# Circuit_Etudiant_2023.net
KiCad netlist of a schematic drawn in Altium Designer
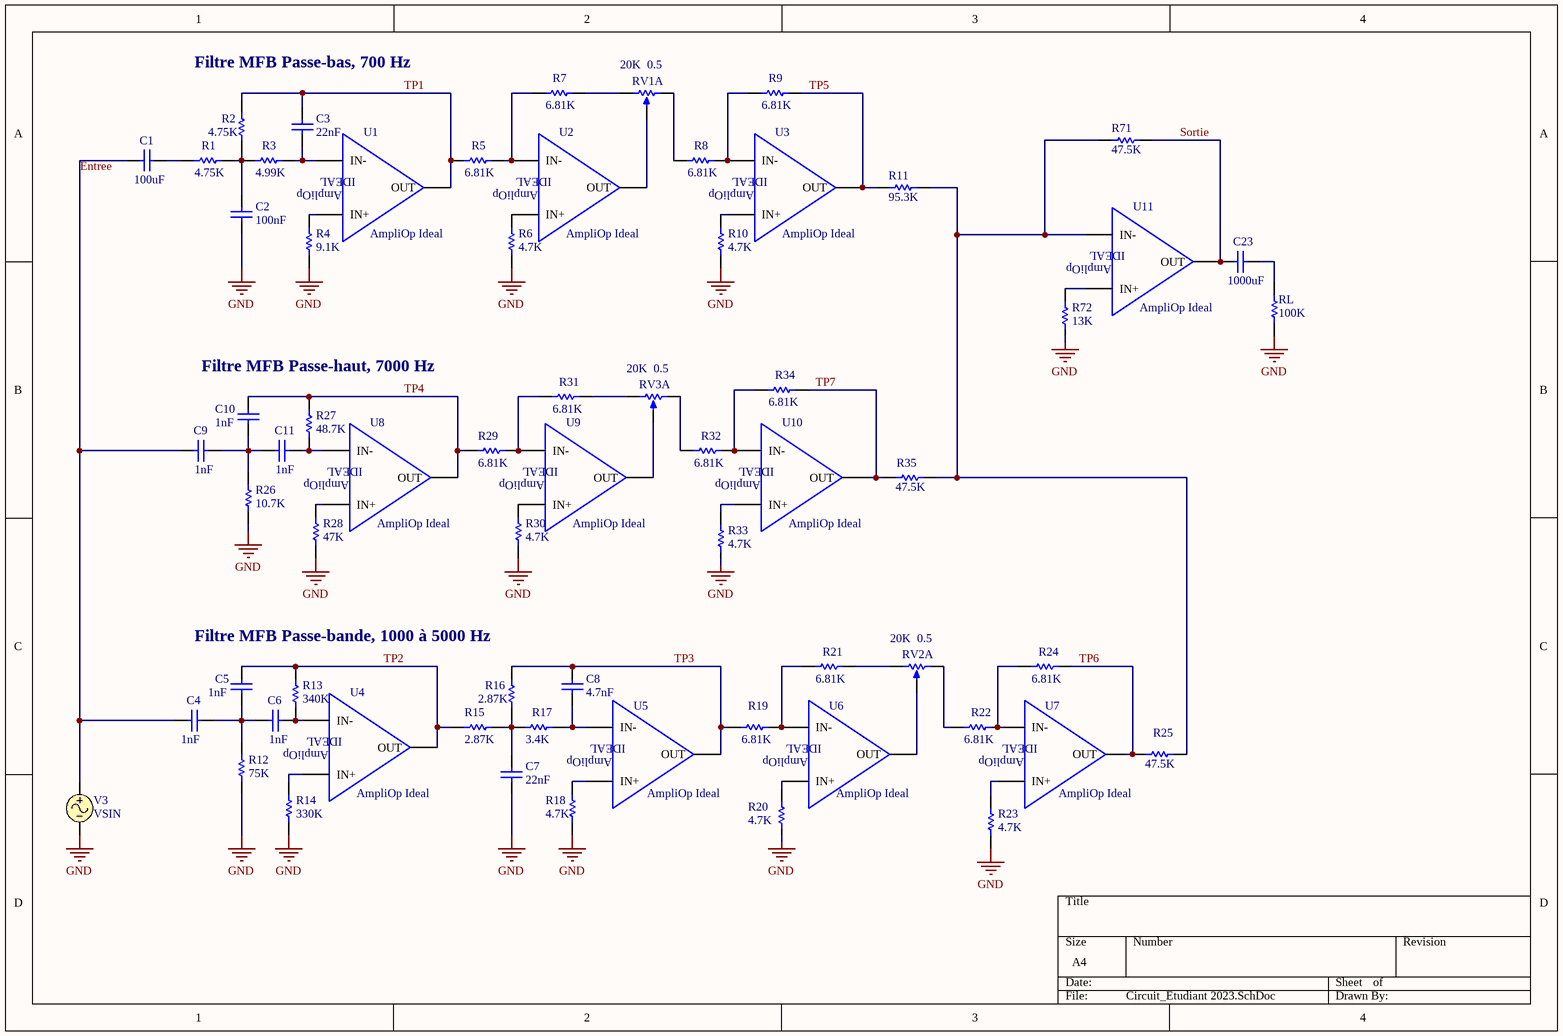
[diagram p0: Circuit_Etudiant 2023.SchDoc]

(export (version "E")
  (design (tool "Eeschema 10.0.6"))
  (components
    (comp (ref "C1")
      (value "100uF")
      (footprint "RAD-0.3")
      (description "Capacitor")
      (fields (field (name "Comment") "Cap") (field (name "PUBLISHER") "Altium Limited"))
      (libsource (lib "Miscellaneous Devices") (part "Cap"))
    )
    (comp (ref "C2")
      (value "100nF")
      (footprint "RAD-0.3")
      (description "Capacitor")
      (fields (field (name "Comment") "Cap") (field (name "PUBLISHER") "Altium Limited"))
      (libsource (lib "Miscellaneous Devices") (part "Cap"))
    )
    (comp (ref "C3")
      (value "22nF")
      (footprint "RAD-0.3")
      (description "Capacitor")
      (fields (field (name "Comment") "Cap") (field (name "PUBLISHER") "Altium Limited"))
      (libsource (lib "Miscellaneous Devices") (part "Cap"))
    )
    (comp (ref "C4")
      (value "1nF")
      (footprint "RAD-0.3")
      (description "Capacitor")
      (fields (field (name "Comment") "Cap") (field (name "PUBLISHER") "Altium Limited"))
      (libsource (lib "Miscellaneous Devices") (part "Cap"))
    )
    (comp (ref "C5")
      (value "1nF")
      (footprint "RAD-0.3")
      (description "Capacitor")
      (fields (field (name "Comment") "Cap") (field (name "PUBLISHER") "Altium Limited"))
      (libsource (lib "Miscellaneous Devices") (part "Cap"))
    )
    (comp (ref "C6")
      (value "1nF")
      (footprint "RAD-0.3")
      (description "Capacitor")
      (fields (field (name "Comment") "Cap") (field (name "PUBLISHER") "Altium Limited"))
      (libsource (lib "Miscellaneous Devices") (part "Cap"))
    )
    (comp (ref "C7")
      (value "22nF")
      (footprint "RAD-0.3")
      (description "Capacitor")
      (fields (field (name "Comment") "Cap") (field (name "PUBLISHER") "Altium Limited"))
      (libsource (lib "Miscellaneous Devices") (part "Cap"))
    )
    (comp (ref "C8")
      (value "4.7nF")
      (footprint "RAD-0.3")
      (description "Capacitor")
      (fields (field (name "Comment") "Cap") (field (name "PUBLISHER") "Altium Limited"))
      (libsource (lib "Miscellaneous Devices") (part "Cap"))
    )
    (comp (ref "C9")
      (value "1nF")
      (footprint "RAD-0.3")
      (description "Capacitor")
      (fields (field (name "Comment") "Cap") (field (name "PUBLISHER") "Altium Limited"))
      (libsource (lib "Miscellaneous Devices") (part "Cap"))
    )
    (comp (ref "C10")
      (value "1nF")
      (footprint "RAD-0.3")
      (description "Capacitor")
      (fields (field (name "Comment") "Cap") (field (name "PUBLISHER") "Altium Limited"))
      (libsource (lib "Miscellaneous Devices") (part "Cap"))
    )
    (comp (ref "C11")
      (value "1nF")
      (footprint "RAD-0.3")
      (description "Capacitor")
      (fields (field (name "Comment") "Cap") (field (name "PUBLISHER") "Altium Limited"))
      (libsource (lib "Miscellaneous Devices") (part "Cap"))
    )
    (comp (ref "C23")
      (value "1000uF")
      (footprint "RAD-0.3")
      (description "Capacitor")
      (fields (field (name "Comment") "Cap") (field (name "PUBLISHER") "Altium Limited"))
      (libsource (lib "Miscellaneous Devices") (part "Cap"))
    )
    (comp (ref "R1")
      (value "4.75K")
      (footprint "AXIAL-0.3")
      (description "Resistor")
      (fields (field (name "Comment") "Res1") (field (name "PUBLISHER") "Altium Limited"))
      (libsource (lib "Miscellaneous Devices") (part "Res1"))
    )
    (comp (ref "R2")
      (value "4.75K")
      (footprint "AXIAL-0.3")
      (description "Resistor")
      (fields (field (name "Comment") "Res1") (field (name "PUBLISHER") "Altium Limited"))
      (libsource (lib "Miscellaneous Devices") (part "Res1"))
    )
    (comp (ref "R3")
      (value "4.99K")
      (footprint "AXIAL-0.3")
      (description "Resistor")
      (fields (field (name "Comment") "Res1") (field (name "PUBLISHER") "Altium Limited"))
      (libsource (lib "Miscellaneous Devices") (part "Res1"))
    )
    (comp (ref "R4")
      (value "9.1K")
      (footprint "AXIAL-0.3")
      (description "Resistor")
      (fields (field (name "Comment") "Res1") (field (name "PUBLISHER") "Altium Limited"))
      (libsource (lib "Miscellaneous Devices") (part "Res1"))
    )
    (comp (ref "R5")
      (value "6.81K")
      (footprint "AXIAL-0.3")
      (description "Resistor")
      (fields (field (name "Comment") "Res1") (field (name "PUBLISHER") "Altium Limited"))
      (libsource (lib "Miscellaneous Devices") (part "Res1"))
    )
    (comp (ref "R6")
      (value "4.7K")
      (footprint "AXIAL-0.3")
      (description "Resistor")
      (fields (field (name "Comment") "Res1") (field (name "PUBLISHER") "Altium Limited"))
      (libsource (lib "Miscellaneous Devices") (part "Res1"))
    )
    (comp (ref "R7")
      (value "6.81K")
      (footprint "AXIAL-0.3")
      (description "Resistor")
      (fields (field (name "Comment") "Res1") (field (name "PUBLISHER") "Altium Limited"))
      (libsource (lib "Miscellaneous Devices") (part "Res1"))
    )
    (comp (ref "R8")
      (value "6.81K")
      (footprint "AXIAL-0.3")
      (description "Resistor")
      (fields (field (name "Comment") "Res1") (field (name "PUBLISHER") "Altium Limited"))
      (libsource (lib "Miscellaneous Devices") (part "Res1"))
    )
    (comp (ref "R9")
      (value "6.81K")
      (footprint "AXIAL-0.3")
      (description "Resistor")
      (fields (field (name "Comment") "Res1") (field (name "PUBLISHER") "Altium Limited"))
      (libsource (lib "Miscellaneous Devices") (part "Res1"))
    )
    (comp (ref "R10")
      (value "4.7K")
      (footprint "AXIAL-0.3")
      (description "Resistor")
      (fields (field (name "Comment") "Res1") (field (name "PUBLISHER") "Altium Limited"))
      (libsource (lib "Miscellaneous Devices") (part "Res1"))
    )
    (comp (ref "R11")
      (value "95.3K")
      (footprint "AXIAL-0.3")
      (description "Resistor")
      (fields (field (name "Comment") "Res1") (field (name "PUBLISHER") "Altium Limited"))
      (libsource (lib "Miscellaneous Devices") (part "Res1"))
    )
    (comp (ref "R12")
      (value "75K")
      (footprint "AXIAL-0.3")
      (description "Resistor")
      (fields (field (name "Comment") "Res1") (field (name "PUBLISHER") "Altium Limited"))
      (libsource (lib "Miscellaneous Devices") (part "Res1"))
    )
    (comp (ref "R13")
      (value "340K")
      (footprint "AXIAL-0.3")
      (description "Resistor")
      (fields (field (name "Comment") "Res1") (field (name "PUBLISHER") "Altium Limited"))
      (libsource (lib "Miscellaneous Devices") (part "Res1"))
    )
    (comp (ref "R14")
      (value "330K")
      (footprint "AXIAL-0.3")
      (description "Resistor")
      (fields (field (name "Comment") "Res1") (field (name "PUBLISHER") "Altium Limited"))
      (libsource (lib "Miscellaneous Devices") (part "Res1"))
    )
    (comp (ref "R15")
      (value "2.87K")
      (footprint "AXIAL-0.3")
      (description "Resistor")
      (fields (field (name "Comment") "Res1") (field (name "PUBLISHER") "Altium Limited"))
      (libsource (lib "Miscellaneous Devices") (part "Res1"))
    )
    (comp (ref "R16")
      (value "2.87K")
      (footprint "AXIAL-0.3")
      (description "Resistor")
      (fields (field (name "Comment") "Res1") (field (name "PUBLISHER") "Altium Limited"))
      (libsource (lib "Miscellaneous Devices") (part "Res1"))
    )
    (comp (ref "R17")
      (value "3.4K")
      (footprint "AXIAL-0.3")
      (description "Resistor")
      (fields (field (name "Comment") "Res1") (field (name "PUBLISHER") "Altium Limited"))
      (libsource (lib "Miscellaneous Devices") (part "Res1"))
    )
    (comp (ref "R18")
      (value "4.7K")
      (footprint "AXIAL-0.3")
      (description "Resistor")
      (fields (field (name "Comment") "Res1") (field (name "PUBLISHER") "Altium Limited"))
      (libsource (lib "Miscellaneous Devices") (part "Res1"))
    )
    (comp (ref "R19")
      (value "6.81K")
      (footprint "AXIAL-0.3")
      (description "Resistor")
      (fields (field (name "Comment") "Res1") (field (name "PUBLISHER") "Altium Limited"))
      (libsource (lib "Miscellaneous Devices") (part "Res1"))
    )
    (comp (ref "R20")
      (value "4.7K")
      (footprint "AXIAL-0.3")
      (description "Resistor")
      (fields (field (name "Comment") "Res1") (field (name "PUBLISHER") "Altium Limited"))
      (libsource (lib "Miscellaneous Devices") (part "Res1"))
    )
    (comp (ref "R21")
      (value "6.81K")
      (footprint "AXIAL-0.3")
      (description "Resistor")
      (fields (field (name "Comment") "Res1") (field (name "PUBLISHER") "Altium Limited"))
      (libsource (lib "Miscellaneous Devices") (part "Res1"))
    )
    (comp (ref "R22")
      (value "6.81K")
      (footprint "AXIAL-0.3")
      (description "Resistor")
      (fields (field (name "Comment") "Res1") (field (name "PUBLISHER") "Altium Limited"))
      (libsource (lib "Miscellaneous Devices") (part "Res1"))
    )
    (comp (ref "R23")
      (value "4.7K")
      (footprint "AXIAL-0.3")
      (description "Resistor")
      (fields (field (name "Comment") "Res1") (field (name "PUBLISHER") "Altium Limited"))
      (libsource (lib "Miscellaneous Devices") (part "Res1"))
    )
    (comp (ref "R24")
      (value "6.81K")
      (footprint "AXIAL-0.3")
      (description "Resistor")
      (fields (field (name "Comment") "Res1") (field (name "PUBLISHER") "Altium Limited"))
      (libsource (lib "Miscellaneous Devices") (part "Res1"))
    )
    (comp (ref "R25")
      (value "47.5K")
      (footprint "AXIAL-0.3")
      (description "Resistor")
      (fields (field (name "Comment") "Res1") (field (name "PUBLISHER") "Altium Limited"))
      (libsource (lib "Miscellaneous Devices") (part "Res1"))
    )
    (comp (ref "R26")
      (value "10.7K")
      (footprint "AXIAL-0.3")
      (description "Resistor")
      (fields (field (name "Comment") "Res1") (field (name "PUBLISHER") "Altium Limited"))
      (libsource (lib "Miscellaneous Devices") (part "Res1"))
    )
    (comp (ref "R27")
      (value "48.7K")
      (footprint "AXIAL-0.3")
      (description "Resistor")
      (fields (field (name "Comment") "Res1") (field (name "PUBLISHER") "Altium Limited"))
      (libsource (lib "Miscellaneous Devices") (part "Res1"))
    )
    (comp (ref "R28")
      (value "47K")
      (footprint "AXIAL-0.3")
      (description "Resistor")
      (fields (field (name "Comment") "Res1") (field (name "PUBLISHER") "Altium Limited"))
      (libsource (lib "Miscellaneous Devices") (part "Res1"))
    )
    (comp (ref "R29")
      (value "6.81K")
      (footprint "AXIAL-0.3")
      (description "Resistor")
      (fields (field (name "Comment") "Res1") (field (name "PUBLISHER") "Altium Limited"))
      (libsource (lib "Miscellaneous Devices") (part "Res1"))
    )
    (comp (ref "R30")
      (value "4.7K")
      (footprint "AXIAL-0.3")
      (description "Resistor")
      (fields (field (name "Comment") "Res1") (field (name "PUBLISHER") "Altium Limited"))
      (libsource (lib "Miscellaneous Devices") (part "Res1"))
    )
    (comp (ref "R31")
      (value "6.81K")
      (footprint "AXIAL-0.3")
      (description "Resistor")
      (fields (field (name "Comment") "Res1") (field (name "PUBLISHER") "Altium Limited"))
      (libsource (lib "Miscellaneous Devices") (part "Res1"))
    )
    (comp (ref "R32")
      (value "6.81K")
      (footprint "AXIAL-0.3")
      (description "Resistor")
      (fields (field (name "Comment") "Res1") (field (name "PUBLISHER") "Altium Limited"))
      (libsource (lib "Miscellaneous Devices") (part "Res1"))
    )
    (comp (ref "R33")
      (value "4.7K")
      (footprint "AXIAL-0.3")
      (description "Resistor")
      (fields (field (name "Comment") "Res1") (field (name "PUBLISHER") "Altium Limited"))
      (libsource (lib "Miscellaneous Devices") (part "Res1"))
    )
    (comp (ref "R34")
      (value "6.81K")
      (footprint "AXIAL-0.3")
      (description "Resistor")
      (fields (field (name "Comment") "Res1") (field (name "PUBLISHER") "Altium Limited"))
      (libsource (lib "Miscellaneous Devices") (part "Res1"))
    )
    (comp (ref "R35")
      (value "47.5K")
      (footprint "AXIAL-0.3")
      (description "Resistor")
      (fields (field (name "Comment") "Res1") (field (name "PUBLISHER") "Altium Limited"))
      (libsource (lib "Miscellaneous Devices") (part "Res1"))
    )
    (comp (ref "R71")
      (value "47.5K")
      (footprint "AXIAL-0.3")
      (description "Resistor")
      (fields (field (name "Comment") "Res1") (field (name "PUBLISHER") "Altium Limited"))
      (libsource (lib "Miscellaneous Devices") (part "Res1"))
    )
    (comp (ref "R72")
      (value "13K")
      (footprint "AXIAL-0.3")
      (description "Resistor")
      (fields (field (name "Comment") "Res1") (field (name "PUBLISHER") "Altium Limited"))
      (libsource (lib "Miscellaneous Devices") (part "Res1"))
    )
    (comp (ref "RL")
      (value "100K")
      (footprint "AXIAL-0.3")
      (description "Resistor")
      (fields (field (name "Comment") "Res1") (field (name "PUBLISHER") "Altium Limited"))
      (libsource (lib "Miscellaneous Devices") (part "Res1"))
    )
    (comp (ref "RV1A")
      (value "20K")
      (footprint "VR5")
      (description "Potentiometer")
      (fields
        (field (name "SET POSITION") "0.5")
        (field (name "Comment") "RPot")
        (field (name "PUBLISHER") "Altium Limited")
      )
      (libsource (lib "Miscellaneous Devices") (part "RPot"))
    )
    (comp (ref "RV2A")
      (value "20K")
      (footprint "VR5")
      (description "Potentiometer")
      (fields
        (field (name "SET POSITION") "0.5")
        (field (name "Comment") "RPot")
        (field (name "PUBLISHER") "Altium Limited")
      )
      (libsource (lib "Miscellaneous Devices") (part "RPot"))
    )
    (comp (ref "RV3A")
      (value "20K")
      (footprint "VR5")
      (description "Potentiometer")
      (fields
        (field (name "SET POSITION") "0.5")
        (field (name "Comment") "RPot")
        (field (name "PUBLISHER") "Altium Limited")
      )
      (libsource (lib "Miscellaneous Devices") (part "RPot"))
    )
    (comp (ref "U1") (value "AmpliOp Ideal") (libsource (lib "Librarie_S2") (part "AmpliOp_ideal")))
    (comp (ref "U2") (value "AmpliOp Ideal") (libsource (lib "Librarie_S2") (part "AmpliOp_ideal")))
    (comp (ref "U3") (value "AmpliOp Ideal") (libsource (lib "Librarie_S2") (part "AmpliOp_ideal")))
    (comp (ref "U4") (value "AmpliOp Ideal") (libsource (lib "Librarie_S2") (part "AmpliOp_ideal")))
    (comp (ref "U5") (value "AmpliOp Ideal") (libsource (lib "Librarie_S2") (part "AmpliOp_ideal")))
    (comp (ref "U6") (value "AmpliOp Ideal") (libsource (lib "Librarie_S2") (part "AmpliOp_ideal")))
    (comp (ref "U7") (value "AmpliOp Ideal") (libsource (lib "Librarie_S2") (part "AmpliOp_ideal")))
    (comp (ref "U8") (value "AmpliOp Ideal") (libsource (lib "Librarie_S2") (part "AmpliOp_ideal")))
    (comp (ref "U9") (value "AmpliOp Ideal") (libsource (lib "Librarie_S2") (part "AmpliOp_ideal")))
    (comp (ref "U10") (value "AmpliOp Ideal") (libsource (lib "Librarie_S2") (part "AmpliOp_ideal")))
    (comp (ref "U11") (value "AmpliOp Ideal") (libsource (lib "Librarie_S2") (part "AmpliOp_ideal")))
    (comp (ref "V3")
      (value "VSIN")
      (description "Sinusoidal Voltage Source")
      (fields (field (name "PUBLISHER") "Altium Limited"))
      (libsource (lib "Simulation Sources") (part "VSIN"))
    )
  )
  (nets
    (net (code "1") (name "/Entree") (class "Default")
      (node (ref "C1") (pin "1") (pinfunction "1_1") (pintype "passive"))
      (node (ref "C4") (pin "1") (pinfunction "1_1") (pintype "passive"))
      (node (ref "C9") (pin "1") (pinfunction "1_1") (pintype "passive"))
      (node (ref "V3") (pin "1") (pinfunction "1_1") (pintype "passive"))
    )
    (net (code "2") (name "/Sortie") (class "Default")
      (node (ref "C23") (pin "1") (pinfunction "1_1") (pintype "passive"))
      (node (ref "R71") (pin "2") (pinfunction "2_2") (pintype "passive"))
      (node (ref "U11") (pin "3") (pinfunction "OUT_3") (pintype "passive"))
    )
    (net (code "3") (name "/TP1") (class "Default")
      (node (ref "C3") (pin "1") (pinfunction "1_1") (pintype "passive"))
      (node (ref "R2") (pin "1") (pinfunction "1_1") (pintype "passive"))
      (node (ref "R5") (pin "1") (pinfunction "1_1") (pintype "passive"))
      (node (ref "U1") (pin "3") (pinfunction "OUT_3") (pintype "passive"))
    )
    (net (code "4") (name "/TP2") (class "Default")
      (node (ref "C5") (pin "1") (pinfunction "1_1") (pintype "passive"))
      (node (ref "R13") (pin "1") (pinfunction "1_1") (pintype "passive"))
      (node (ref "R15") (pin "1") (pinfunction "1_1") (pintype "passive"))
      (node (ref "U4") (pin "3") (pinfunction "OUT_3") (pintype "passive"))
    )
    (net (code "5") (name "/TP3") (class "Default")
      (node (ref "C8") (pin "1") (pinfunction "1_1") (pintype "passive"))
      (node (ref "R16") (pin "1") (pinfunction "1_1") (pintype "passive"))
      (node (ref "R19") (pin "1") (pinfunction "1_1") (pintype "passive"))
      (node (ref "U5") (pin "3") (pinfunction "OUT_3") (pintype "passive"))
    )
    (net (code "6") (name "/TP4") (class "Default")
      (node (ref "C10") (pin "1") (pinfunction "1_1") (pintype "passive"))
      (node (ref "R27") (pin "1") (pinfunction "1_1") (pintype "passive"))
      (node (ref "R29") (pin "1") (pinfunction "1_1") (pintype "passive"))
      (node (ref "U8") (pin "3") (pinfunction "OUT_3") (pintype "passive"))
    )
    (net (code "7") (name "/TP5") (class "Default")
      (node (ref "R11") (pin "1") (pinfunction "1_1") (pintype "passive"))
      (node (ref "R9") (pin "2") (pinfunction "2_2") (pintype "passive"))
      (node (ref "U3") (pin "3") (pinfunction "OUT_3") (pintype "passive"))
    )
    (net (code "8") (name "/TP6") (class "Default")
      (node (ref "R24") (pin "2") (pinfunction "2_2") (pintype "passive"))
      (node (ref "R25") (pin "1") (pinfunction "1_1") (pintype "passive"))
      (node (ref "U7") (pin "3") (pinfunction "OUT_3") (pintype "passive"))
    )
    (net (code "9") (name "/TP7") (class "Default")
      (node (ref "R34") (pin "2") (pinfunction "2_2") (pintype "passive"))
      (node (ref "R35") (pin "1") (pinfunction "1_1") (pintype "passive"))
      (node (ref "U10") (pin "3") (pinfunction "OUT_3") (pintype "passive"))
    )
    (net (code "10") (name "GND") (class "Default")
      (node (ref "C2") (pin "2") (pinfunction "2_2") (pintype "passive"))
      (node (ref "C7") (pin "2") (pinfunction "2_2") (pintype "passive"))
      (node (ref "R10") (pin "2") (pinfunction "2_2") (pintype "passive"))
      (node (ref "R12") (pin "2") (pinfunction "2_2") (pintype "passive"))
      (node (ref "R14") (pin "2") (pinfunction "2_2") (pintype "passive"))
      (node (ref "R18") (pin "2") (pinfunction "2_2") (pintype "passive"))
      (node (ref "R20") (pin "2") (pinfunction "2_2") (pintype "passive"))
      (node (ref "R23") (pin "2") (pinfunction "2_2") (pintype "passive"))
      (node (ref "R26") (pin "2") (pinfunction "2_2") (pintype "passive"))
      (node (ref "R28") (pin "2") (pinfunction "2_2") (pintype "passive"))
      (node (ref "R30") (pin "2") (pinfunction "2_2") (pintype "passive"))
      (node (ref "R33") (pin "2") (pinfunction "2_2") (pintype "passive"))
      (node (ref "R4") (pin "2") (pinfunction "2_2") (pintype "passive"))
      (node (ref "R6") (pin "2") (pinfunction "2_2") (pintype "passive"))
      (node (ref "R72") (pin "2") (pinfunction "2_2") (pintype "passive"))
      (node (ref "RL") (pin "1") (pinfunction "1_1") (pintype "passive"))
      (node (ref "V3") (pin "2") (pinfunction "2_2") (pintype "passive"))
    )
    (net (code "11") (name "Net-(C1-Pad2)") (class "Default")
      (node (ref "C1") (pin "2") (pinfunction "2_2") (pintype "passive"))
      (node (ref "R1") (pin "1") (pinfunction "1_1") (pintype "passive"))
    )
    (net (code "12") (name "Net-(C2-Pad1)") (class "Default")
      (node (ref "C2") (pin "1") (pinfunction "1_1") (pintype "passive"))
      (node (ref "R1") (pin "2") (pinfunction "2_2") (pintype "passive"))
      (node (ref "R2") (pin "2") (pinfunction "2_2") (pintype "passive"))
      (node (ref "R3") (pin "1") (pinfunction "1_1") (pintype "passive"))
    )
    (net (code "13") (name "Net-(C4-Pad2)") (class "Default")
      (node (ref "C4") (pin "2") (pinfunction "2_2") (pintype "passive"))
      (node (ref "C5") (pin "2") (pinfunction "2_2") (pintype "passive"))
      (node (ref "C6") (pin "1") (pinfunction "1_1") (pintype "passive"))
      (node (ref "R12") (pin "1") (pinfunction "1_1") (pintype "passive"))
    )
    (net (code "14") (name "Net-(C7-Pad1)") (class "Default")
      (node (ref "C7") (pin "1") (pinfunction "1_1") (pintype "passive"))
      (node (ref "R15") (pin "2") (pinfunction "2_2") (pintype "passive"))
      (node (ref "R16") (pin "2") (pinfunction "2_2") (pintype "passive"))
      (node (ref "R17") (pin "1") (pinfunction "1_1") (pintype "passive"))
    )
    (net (code "15") (name "Net-(C10-Pad2)") (class "Default")
      (node (ref "C10") (pin "2") (pinfunction "2_2") (pintype "passive"))
      (node (ref "C11") (pin "1") (pinfunction "1_1") (pintype "passive"))
      (node (ref "C9") (pin "2") (pinfunction "2_2") (pintype "passive"))
      (node (ref "R26") (pin "1") (pinfunction "1_1") (pintype "passive"))
    )
    (net (code "16") (name "Net-(C23-Pad2)") (class "Default")
      (node (ref "C23") (pin "2") (pinfunction "2_2") (pintype "passive"))
      (node (ref "RL") (pin "2") (pinfunction "2_2") (pintype "passive"))
    )
    (net (code "17") (name "Net-(RV1A-BOT)") (class "Default")
      (node (ref "R8") (pin "1") (pinfunction "1_1") (pintype "passive"))
      (node (ref "RV1A") (pin "2") (pinfunction "BOT_2") (pintype "passive"))
    )
    (net (code "18") (name "Net-(RV1A-TAP)") (class "Default")
      (node (ref "RV1A") (pin "3") (pinfunction "TAP_3") (pintype "passive"))
      (node (ref "U2") (pin "3") (pinfunction "OUT_3") (pintype "passive"))
    )
    (net (code "19") (name "Net-(RV1A-TOP)") (class "Default")
      (node (ref "R7") (pin "2") (pinfunction "2_2") (pintype "passive"))
      (node (ref "RV1A") (pin "1") (pinfunction "TOP_1") (pintype "passive"))
    )
    (net (code "20") (name "Net-(RV2A-BOT)") (class "Default")
      (node (ref "R22") (pin "1") (pinfunction "1_1") (pintype "passive"))
      (node (ref "RV2A") (pin "2") (pinfunction "BOT_2") (pintype "passive"))
    )
    (net (code "21") (name "Net-(RV2A-TAP)") (class "Default")
      (node (ref "RV2A") (pin "3") (pinfunction "TAP_3") (pintype "passive"))
      (node (ref "U6") (pin "3") (pinfunction "OUT_3") (pintype "passive"))
    )
    (net (code "22") (name "Net-(RV2A-TOP)") (class "Default")
      (node (ref "R21") (pin "2") (pinfunction "2_2") (pintype "passive"))
      (node (ref "RV2A") (pin "1") (pinfunction "TOP_1") (pintype "passive"))
    )
    (net (code "23") (name "Net-(RV3A-BOT)") (class "Default")
      (node (ref "R32") (pin "1") (pinfunction "1_1") (pintype "passive"))
      (node (ref "RV3A") (pin "2") (pinfunction "BOT_2") (pintype "passive"))
    )
    (net (code "24") (name "Net-(RV3A-TAP)") (class "Default")
      (node (ref "RV3A") (pin "3") (pinfunction "TAP_3") (pintype "passive"))
      (node (ref "U9") (pin "3") (pinfunction "OUT_3") (pintype "passive"))
    )
    (net (code "25") (name "Net-(RV3A-TOP)") (class "Default")
      (node (ref "R31") (pin "2") (pinfunction "2_2") (pintype "passive"))
      (node (ref "RV3A") (pin "1") (pinfunction "TOP_1") (pintype "passive"))
    )
    (net (code "26") (name "Net-(U1-IN+)") (class "Default")
      (node (ref "R4") (pin "1") (pinfunction "1_1") (pintype "passive"))
      (node (ref "U1") (pin "1") (pinfunction "IN+_1") (pintype "passive"))
    )
    (net (code "27") (name "Net-(U1-IN-)") (class "Default")
      (node (ref "C3") (pin "2") (pinfunction "2_2") (pintype "passive"))
      (node (ref "R3") (pin "2") (pinfunction "2_2") (pintype "passive"))
      (node (ref "U1") (pin "2") (pinfunction "IN-_2") (pintype "passive"))
    )
    (net (code "28") (name "Net-(U2-IN+)") (class "Default")
      (node (ref "R6") (pin "1") (pinfunction "1_1") (pintype "passive"))
      (node (ref "U2") (pin "1") (pinfunction "IN+_1") (pintype "passive"))
    )
    (net (code "29") (name "Net-(U2-IN-)") (class "Default")
      (node (ref "R5") (pin "2") (pinfunction "2_2") (pintype "passive"))
      (node (ref "R7") (pin "1") (pinfunction "1_1") (pintype "passive"))
      (node (ref "U2") (pin "2") (pinfunction "IN-_2") (pintype "passive"))
    )
    (net (code "30") (name "Net-(U3-IN+)") (class "Default")
      (node (ref "R10") (pin "1") (pinfunction "1_1") (pintype "passive"))
      (node (ref "U3") (pin "1") (pinfunction "IN+_1") (pintype "passive"))
    )
    (net (code "31") (name "Net-(U3-IN-)") (class "Default")
      (node (ref "R8") (pin "2") (pinfunction "2_2") (pintype "passive"))
      (node (ref "R9") (pin "1") (pinfunction "1_1") (pintype "passive"))
      (node (ref "U3") (pin "2") (pinfunction "IN-_2") (pintype "passive"))
    )
    (net (code "32") (name "Net-(U4-IN+)") (class "Default")
      (node (ref "R14") (pin "1") (pinfunction "1_1") (pintype "passive"))
      (node (ref "U4") (pin "1") (pinfunction "IN+_1") (pintype "passive"))
    )
    (net (code "33") (name "Net-(U4-IN-)") (class "Default")
      (node (ref "C6") (pin "2") (pinfunction "2_2") (pintype "passive"))
      (node (ref "R13") (pin "2") (pinfunction "2_2") (pintype "passive"))
      (node (ref "U4") (pin "2") (pinfunction "IN-_2") (pintype "passive"))
    )
    (net (code "34") (name "Net-(U5-IN+)") (class "Default")
      (node (ref "R18") (pin "1") (pinfunction "1_1") (pintype "passive"))
      (node (ref "U5") (pin "1") (pinfunction "IN+_1") (pintype "passive"))
    )
    (net (code "35") (name "Net-(U5-IN-)") (class "Default")
      (node (ref "C8") (pin "2") (pinfunction "2_2") (pintype "passive"))
      (node (ref "R17") (pin "2") (pinfunction "2_2") (pintype "passive"))
      (node (ref "U5") (pin "2") (pinfunction "IN-_2") (pintype "passive"))
    )
    (net (code "36") (name "Net-(U6-IN+)") (class "Default")
      (node (ref "R20") (pin "1") (pinfunction "1_1") (pintype "passive"))
      (node (ref "U6") (pin "1") (pinfunction "IN+_1") (pintype "passive"))
    )
    (net (code "37") (name "Net-(U6-IN-)") (class "Default")
      (node (ref "R19") (pin "2") (pinfunction "2_2") (pintype "passive"))
      (node (ref "R21") (pin "1") (pinfunction "1_1") (pintype "passive"))
      (node (ref "U6") (pin "2") (pinfunction "IN-_2") (pintype "passive"))
    )
    (net (code "38") (name "Net-(U7-IN+)") (class "Default")
      (node (ref "R23") (pin "1") (pinfunction "1_1") (pintype "passive"))
      (node (ref "U7") (pin "1") (pinfunction "IN+_1") (pintype "passive"))
    )
    (net (code "39") (name "Net-(U7-IN-)") (class "Default")
      (node (ref "R22") (pin "2") (pinfunction "2_2") (pintype "passive"))
      (node (ref "R24") (pin "1") (pinfunction "1_1") (pintype "passive"))
      (node (ref "U7") (pin "2") (pinfunction "IN-_2") (pintype "passive"))
    )
    (net (code "40") (name "Net-(U8-IN+)") (class "Default")
      (node (ref "R28") (pin "1") (pinfunction "1_1") (pintype "passive"))
      (node (ref "U8") (pin "1") (pinfunction "IN+_1") (pintype "passive"))
    )
    (net (code "41") (name "Net-(U8-IN-)") (class "Default")
      (node (ref "C11") (pin "2") (pinfunction "2_2") (pintype "passive"))
      (node (ref "R27") (pin "2") (pinfunction "2_2") (pintype "passive"))
      (node (ref "U8") (pin "2") (pinfunction "IN-_2") (pintype "passive"))
    )
    (net (code "42") (name "Net-(U9-IN+)") (class "Default")
      (node (ref "R30") (pin "1") (pinfunction "1_1") (pintype "passive"))
      (node (ref "U9") (pin "1") (pinfunction "IN+_1") (pintype "passive"))
    )
    (net (code "43") (name "Net-(U9-IN-)") (class "Default")
      (node (ref "R29") (pin "2") (pinfunction "2_2") (pintype "passive"))
      (node (ref "R31") (pin "1") (pinfunction "1_1") (pintype "passive"))
      (node (ref "U9") (pin "2") (pinfunction "IN-_2") (pintype "passive"))
    )
    (net (code "44") (name "Net-(U10-IN+)") (class "Default")
      (node (ref "R33") (pin "1") (pinfunction "1_1") (pintype "passive"))
      (node (ref "U10") (pin "1") (pinfunction "IN+_1") (pintype "passive"))
    )
    (net (code "45") (name "Net-(U10-IN-)") (class "Default")
      (node (ref "R32") (pin "2") (pinfunction "2_2") (pintype "passive"))
      (node (ref "R34") (pin "1") (pinfunction "1_1") (pintype "passive"))
      (node (ref "U10") (pin "2") (pinfunction "IN-_2") (pintype "passive"))
    )
    (net (code "46") (name "Net-(U11-IN+)") (class "Default")
      (node (ref "R72") (pin "1") (pinfunction "1_1") (pintype "passive"))
      (node (ref "U11") (pin "1") (pinfunction "IN+_1") (pintype "passive"))
    )
    (net (code "47") (name "Net-(U11-IN-)") (class "Default")
      (node (ref "R11") (pin "2") (pinfunction "2_2") (pintype "passive"))
      (node (ref "R25") (pin "2") (pinfunction "2_2") (pintype "passive"))
      (node (ref "R35") (pin "2") (pinfunction "2_2") (pintype "passive"))
      (node (ref "R71") (pin "1") (pinfunction "1_1") (pintype "passive"))
      (node (ref "U11") (pin "2") (pinfunction "IN-_2") (pintype "passive"))
    )
  )
)
